# design.net
KiCad netlist of a schematic drawn in Altium Designer
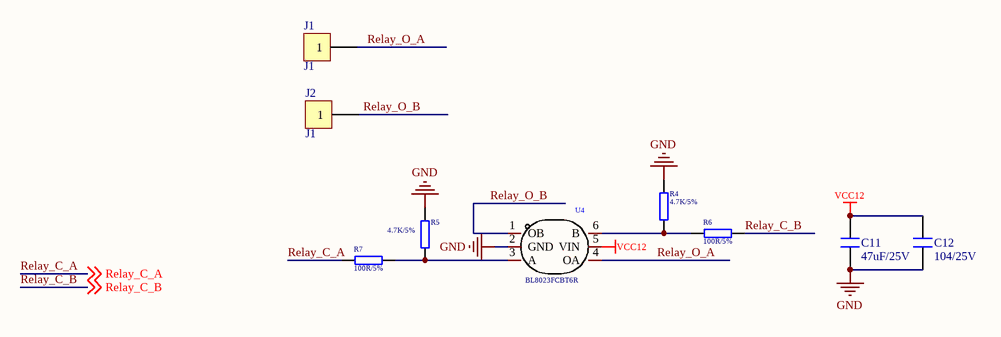
[diagram p0: 继电器.SchDoc]

(export (version "E")
  (design (tool "Eeschema 10.0.6"))
  (components
    (comp (ref "C11") (value "47uF/25V") (footprint "0603R") (libsource (lib "ES_Schematic") (part "CAP_1")))
    (comp (ref "C12") (value "104/25V") (footprint "0603R") (libsource (lib "ES_Schematic") (part "CAP_1")))
    (comp (ref "J1") (value "J1") (footprint "贴片焊盘V1（3*2椭圆）") (libsource (lib "ES_Schematic") (part "J1")))
    (comp (ref "J2") (value "J1") (footprint "贴片焊盘V1（3*2椭圆）") (libsource (lib "ES_Schematic") (part "J1")))
    (comp (ref "R4") (value "4.7K/5%") (footprint "0603R") (libsource (lib "ES_Schematic") (part "RES")))
    (comp (ref "R5") (value "4.7K/5%") (footprint "0603R") (libsource (lib "ES_Schematic") (part "RES")))
    (comp (ref "R6") (value "100R/5%") (footprint "0603R") (libsource (lib "ES_Schematic") (part "RES")))
    (comp (ref "R7") (value "100R/5%") (footprint "0603R") (libsource (lib "ES_Schematic") (part "RES")))
    (comp (ref "U4")
      (value "BL8023FCBT6R")
      (footprint "SOT-23-6")
      (fields (field (name "MANUFACTURER") "BL(上海贝岭)") (field (name "MANUFACTURER PART") "BL8023HCB6TR"))
      (libsource (lib "altium-import") (part "root_0_BL8023HCB6TR_"))
    )
  )
  (nets
    (net (code "1") (name "/Relay_O_A") (class "Default")
      (node (ref "J1") (pin "1") (pinfunction "1_1") (pintype "passive"))
      (node (ref "U4") (pin "4") (pinfunction "OA_4") (pintype "passive"))
    )
    (net (code "2") (name "/Relay_O_B") (class "Default")
      (node (ref "J2") (pin "1") (pinfunction "1_1") (pintype "passive"))
      (node (ref "U4") (pin "1") (pinfunction "OB_1") (pintype "passive"))
    )
    (net (code "3") (name "GND") (class "Default")
      (node (ref "C11") (pin "1") (pinfunction "1_1") (pintype "passive"))
      (node (ref "C12") (pin "1") (pinfunction "1_1") (pintype "passive"))
      (node (ref "R4") (pin "1") (pinfunction "1_1") (pintype "passive"))
      (node (ref "R5") (pin "1") (pinfunction "1_1") (pintype "passive"))
      (node (ref "U4") (pin "2") (pinfunction "GND_2") (pintype "passive"))
    )
    (net (code "4") (name "Net-(U4-A)") (class "Default")
      (node (ref "R5") (pin "2") (pinfunction "2_2") (pintype "passive"))
      (node (ref "R7") (pin "1") (pinfunction "1_1") (pintype "passive"))
      (node (ref "U4") (pin "3") (pinfunction "A_3") (pintype "passive"))
    )
    (net (code "5") (name "Net-(U4-B)") (class "Default")
      (node (ref "R4") (pin "2") (pinfunction "2_2") (pintype "passive"))
      (node (ref "R6") (pin "2") (pinfunction "2_2") (pintype "passive"))
      (node (ref "U4") (pin "6") (pinfunction "B_6") (pintype "passive"))
    )
    (net (code "6") (name "Relay_C_A") (class "Default")
      (node (ref "R7") (pin "2") (pinfunction "2_2") (pintype "passive"))
    )
    (net (code "7") (name "Relay_C_B") (class "Default")
      (node (ref "R6") (pin "1") (pinfunction "1_1") (pintype "passive"))
    )
    (net (code "8") (name "VCC12") (class "Default")
      (node (ref "C11") (pin "2") (pinfunction "2_2") (pintype "passive"))
      (node (ref "C12") (pin "2") (pinfunction "2_2") (pintype "passive"))
      (node (ref "U4") (pin "5") (pinfunction "VIN_5") (pintype "passive"))
    )
  )
)
